# adapterplatine.net
KiCad netlist of a schematic drawn in EAGLE
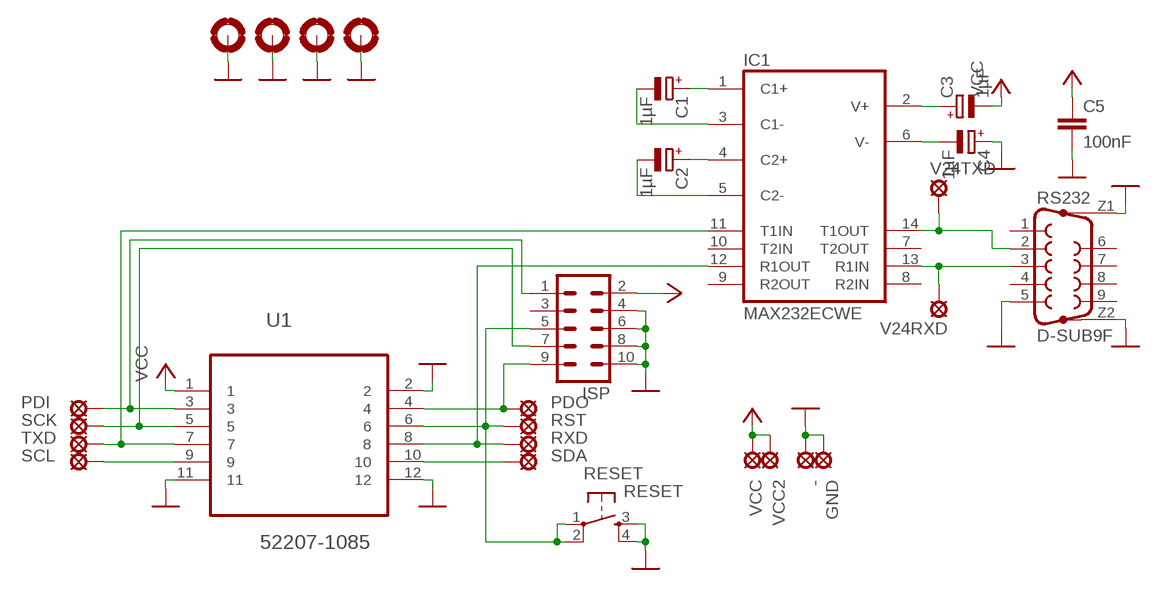
[diagram p0: schematic, sheet 1]

(export (version "E")
  (design (tool "Eeschema 10.0.6"))
  (components
    (comp (ref "-")
      (value "SE11")
      (footprint "eagle-import:SE11")
      (libsource (lib "eagle-import") (part "SE11"))
    )
    (comp (ref "C1")
      (value "1µF")
      (footprint "eagle-import:CT3216")
      (libsource (lib "eagle-import") (part "CPOL-EUCT3216"))
    )
    (comp (ref "C2")
      (value "1µF")
      (footprint "eagle-import:CT3216")
      (libsource (lib "eagle-import") (part "CPOL-EUCT3216"))
    )
    (comp (ref "C3")
      (value "1µF")
      (footprint "eagle-import:CT3216")
      (libsource (lib "eagle-import") (part "CPOL-EUCT3216"))
    )
    (comp (ref "C4")
      (value "1µF")
      (footprint "eagle-import:CT3216")
      (libsource (lib "eagle-import") (part "CPOL-EUCT3216"))
    )
    (comp (ref "C5")
      (value "100nF")
      (footprint "eagle-import:C1206")
      (libsource (lib "eagle-import") (part "C-EUC1206"))
    )
    (comp (ref "GND")
      (value "SE11")
      (footprint "eagle-import:SE11")
      (libsource (lib "eagle-import") (part "SE11"))
    )
    (comp (ref "IC1")
      (value "MAX232ECWE")
      (footprint "eagle-import:SO16L")
      (fields (field (name "MF") "MAXIM") (field (name "MPN") "MAX232ECWE+"))
      (libsource (lib "eagle-import") (part "MAX232ECWE"))
    )
    (comp (ref "ISP")
      (value "ML10")
      (footprint "eagle-import:ML10")
      (libsource (lib "eagle-import") (part "ML10"))
    )
    (comp (ref "PDI")
      (value "SE11")
      (footprint "eagle-import:SE11")
      (libsource (lib "eagle-import") (part "SE11"))
    )
    (comp (ref "PDO")
      (value "SE11")
      (footprint "eagle-import:SE11")
      (libsource (lib "eagle-import") (part "SE11"))
    )
    (comp (ref "RESET")
      (value "RESET")
      (footprint "eagle-import:TASTER")
      (libsource (lib "eagle-import") (part "TASTER"))
    )
    (comp (ref "RS232")
      (value "D-SUB9F")
      (footprint "eagle-import:D-SUB9F")
      (libsource (lib "eagle-import") (part "D-SUB9F"))
    )
    (comp (ref "RST")
      (value "SE11")
      (footprint "eagle-import:SE11")
      (libsource (lib "eagle-import") (part "SE11"))
    )
    (comp (ref "RXD")
      (value "SE11")
      (footprint "eagle-import:SE11")
      (libsource (lib "eagle-import") (part "SE11"))
    )
    (comp (ref "SCK")
      (value "SE11")
      (footprint "eagle-import:SE11")
      (libsource (lib "eagle-import") (part "SE11"))
    )
    (comp (ref "SCL")
      (value "SE11")
      (footprint "eagle-import:SE11")
      (libsource (lib "eagle-import") (part "SE11"))
    )
    (comp (ref "SDA")
      (value "SE11")
      (footprint "eagle-import:SE11")
      (libsource (lib "eagle-import") (part "SE11"))
    )
    (comp (ref "TXD")
      (value "SE11")
      (footprint "eagle-import:SE11")
      (libsource (lib "eagle-import") (part "SE11"))
    )
    (comp (ref "U$1")
      (value "LOCH")
      (footprint "eagle-import:LOCH")
      (libsource (lib "eagle-import") (part "LOCH"))
    )
    (comp (ref "U$2")
      (value "LOCH")
      (footprint "eagle-import:LOCH")
      (libsource (lib "eagle-import") (part "LOCH"))
    )
    (comp (ref "U$3")
      (value "LOCH")
      (footprint "eagle-import:LOCH")
      (libsource (lib "eagle-import") (part "LOCH"))
    )
    (comp (ref "U$4")
      (value "LOCH")
      (footprint "eagle-import:LOCH")
      (libsource (lib "eagle-import") (part "LOCH"))
    )
    (comp (ref "U1")
      (value "52207-1085")
      (footprint "eagle-import:MOLEX_52207-1085")
      (libsource (lib "eagle-import") (part "52207-1085"))
    )
    (comp (ref "V24RXD")
      (value "SE11")
      (footprint "eagle-import:SE11")
      (libsource (lib "eagle-import") (part "SE11"))
    )
    (comp (ref "V24TXD")
      (value "SE11")
      (footprint "eagle-import:SE11")
      (libsource (lib "eagle-import") (part "SE11"))
    )
    (comp (ref "VCC")
      (value "SE11")
      (footprint "eagle-import:SE11")
      (libsource (lib "eagle-import") (part "SE11"))
    )
    (comp (ref "VCC2")
      (value "SE11")
      (footprint "eagle-import:SE11")
      (libsource (lib "eagle-import") (part "SE11"))
    )
  )
  (nets
    (net (code "1") (name "GND") (class "Default")
      (node (ref "-") (pin "MP") (pinfunction "MP_MP") (pintype "passive"))
      (node (ref "C4") (pin "+") (pinfunction "+_+") (pintype "passive"))
      (node (ref "C5") (pin "2") (pinfunction "2_2") (pintype "passive"))
      (node (ref "GND") (pin "MP") (pinfunction "MP_MP") (pintype "passive"))
      (node (ref "ISP") (pin "10") (pinfunction "10_10") (pintype "passive"))
      (node (ref "ISP") (pin "4") (pinfunction "4_4") (pintype "passive"))
      (node (ref "ISP") (pin "6") (pinfunction "6_6") (pintype "passive"))
      (node (ref "ISP") (pin "8") (pinfunction "8_8") (pintype "passive"))
      (node (ref "RESET") (pin "3") (pinfunction "3_3") (pintype "passive"))
      (node (ref "RESET") (pin "4") (pinfunction "4_4") (pintype "passive"))
      (node (ref "RS232") (pin "5") (pinfunction "5_5") (pintype "passive"))
      (node (ref "RS232") (pin "Z1") (pinfunction "G1_Z1") (pintype "passive"))
      (node (ref "RS232") (pin "Z2") (pinfunction "G2_Z2") (pintype "passive"))
      (node (ref "U$1") (pin "B3,0") (pinfunction "MOUNT_B3,0") (pintype "passive"))
      (node (ref "U$2") (pin "B3,0") (pinfunction "MOUNT_B3,0") (pintype "passive"))
      (node (ref "U$3") (pin "B3,0") (pinfunction "MOUNT_B3,0") (pintype "passive"))
      (node (ref "U$4") (pin "B3,0") (pinfunction "MOUNT_B3,0") (pintype "passive"))
      (node (ref "U1") (pin "11") (pinfunction "11_11") (pintype "passive"))
      (node (ref "U1") (pin "12") (pinfunction "12_12") (pintype "passive"))
      (node (ref "U1") (pin "2") (pinfunction "2_2") (pintype "passive"))
    )
    (net (code "2") (name "Net-(IC1A-C1+)") (class "Default")
      (node (ref "C1") (pin "+") (pinfunction "+_+") (pintype "passive"))
      (node (ref "IC1") (pin "1") (pinfunction "C1+_1") (pintype "bidirectional"))
    )
    (net (code "3") (name "Net-(IC1A-C1-)") (class "Default")
      (node (ref "C1") (pin "-") (pinfunction "-_-") (pintype "passive"))
      (node (ref "IC1") (pin "3") (pinfunction "C1-_3") (pintype "bidirectional"))
    )
    (net (code "4") (name "Net-(IC1A-C2+)") (class "Default")
      (node (ref "C2") (pin "+") (pinfunction "+_+") (pintype "passive"))
      (node (ref "IC1") (pin "4") (pinfunction "C2+_4") (pintype "bidirectional"))
    )
    (net (code "5") (name "Net-(IC1A-C2-)") (class "Default")
      (node (ref "C2") (pin "-") (pinfunction "-_-") (pintype "passive"))
      (node (ref "IC1") (pin "5") (pinfunction "C2-_5") (pintype "bidirectional"))
    )
    (net (code "6") (name "Net-(IC1A-R1IN)") (class "Default")
      (node (ref "IC1") (pin "13") (pinfunction "R1IN_13") (pintype "input"))
      (node (ref "RS232") (pin "3") (pinfunction "3_3") (pintype "passive"))
      (node (ref "V24RXD") (pin "MP") (pinfunction "MP_MP") (pintype "passive"))
    )
    (net (code "7") (name "Net-(IC1A-R1OUT)") (class "Default")
      (node (ref "IC1") (pin "12") (pinfunction "R1OUT_12") (pintype "output"))
      (node (ref "RXD") (pin "MP") (pinfunction "MP_MP") (pintype "passive"))
      (node (ref "U1") (pin "8") (pinfunction "8_8") (pintype "passive"))
    )
    (net (code "8") (name "Net-(IC1A-T1IN)") (class "Default")
      (node (ref "IC1") (pin "11") (pinfunction "T1IN_11") (pintype "input"))
      (node (ref "TXD") (pin "MP") (pinfunction "MP_MP") (pintype "passive"))
      (node (ref "U1") (pin "7") (pinfunction "7_7") (pintype "passive"))
    )
    (net (code "9") (name "Net-(IC1A-T1OUT)") (class "Default")
      (node (ref "IC1") (pin "14") (pinfunction "T1OUT_14") (pintype "output"))
      (node (ref "RS232") (pin "2") (pinfunction "2_2") (pintype "passive"))
      (node (ref "V24TXD") (pin "MP") (pinfunction "MP_MP") (pintype "passive"))
    )
    (net (code "10") (name "Net-(IC1A-V+)") (class "Default")
      (node (ref "C3") (pin "+") (pinfunction "+_+") (pintype "passive"))
      (node (ref "IC1") (pin "2") (pinfunction "V+_2") (pintype "bidirectional"))
    )
    (net (code "11") (name "Net-(IC1A-V-)") (class "Default")
      (node (ref "C4") (pin "-") (pinfunction "-_-") (pintype "passive"))
      (node (ref "IC1") (pin "6") (pinfunction "V-_6") (pintype "bidirectional"))
    )
    (net (code "12") (name "Net-(ISP-Pad1)") (class "Default")
      (node (ref "ISP") (pin "1") (pinfunction "1_1") (pintype "passive"))
      (node (ref "PDI") (pin "MP") (pinfunction "MP_MP") (pintype "passive"))
      (node (ref "U1") (pin "3") (pinfunction "3_3") (pintype "passive"))
    )
    (net (code "13") (name "Net-(ISP-Pad5)") (class "Default")
      (node (ref "ISP") (pin "5") (pinfunction "5_5") (pintype "passive"))
      (node (ref "RESET") (pin "1") (pinfunction "1_1") (pintype "passive"))
      (node (ref "RESET") (pin "2") (pinfunction "2_2") (pintype "passive"))
      (node (ref "RST") (pin "MP") (pinfunction "MP_MP") (pintype "passive"))
      (node (ref "U1") (pin "6") (pinfunction "6_6") (pintype "passive"))
    )
    (net (code "14") (name "Net-(ISP-Pad7)") (class "Default")
      (node (ref "ISP") (pin "7") (pinfunction "7_7") (pintype "passive"))
      (node (ref "SCK") (pin "MP") (pinfunction "MP_MP") (pintype "passive"))
      (node (ref "U1") (pin "5") (pinfunction "5_5") (pintype "passive"))
    )
    (net (code "15") (name "Net-(ISP-Pad9)") (class "Default")
      (node (ref "ISP") (pin "9") (pinfunction "9_9") (pintype "passive"))
      (node (ref "PDO") (pin "MP") (pinfunction "MP_MP") (pintype "passive"))
      (node (ref "U1") (pin "4") (pinfunction "4_4") (pintype "passive"))
    )
    (net (code "16") (name "Net-(SCL-PadMP)") (class "Default")
      (node (ref "SCL") (pin "MP") (pinfunction "MP_MP") (pintype "passive"))
      (node (ref "U1") (pin "9") (pinfunction "9_9") (pintype "passive"))
    )
    (net (code "17") (name "Net-(SDA-PadMP)") (class "Default")
      (node (ref "SDA") (pin "MP") (pinfunction "MP_MP") (pintype "passive"))
      (node (ref "U1") (pin "10") (pinfunction "10_10") (pintype "passive"))
    )
    (net (code "18") (name "VCC") (class "Default")
      (node (ref "C3") (pin "-") (pinfunction "-_-") (pintype "passive"))
      (node (ref "C5") (pin "1") (pinfunction "1_1") (pintype "passive"))
      (node (ref "ISP") (pin "2") (pinfunction "2_2") (pintype "passive"))
      (node (ref "U1") (pin "1") (pinfunction "1_1") (pintype "passive"))
      (node (ref "VCC") (pin "MP") (pinfunction "MP_MP") (pintype "passive"))
      (node (ref "VCC2") (pin "MP") (pinfunction "MP_MP") (pintype "passive"))
    )
    (net (code "19") (name "unconnected-(IC1A-R2IN-Pad8)") (class "Default")
      (node (ref "IC1") (pin "8") (pinfunction "R2IN_8") (pintype "input"))
    )
    (net (code "20") (name "unconnected-(IC1A-R2OUT-Pad9)") (class "Default")
      (node (ref "IC1") (pin "9") (pinfunction "R2OUT_9") (pintype "output"))
    )
    (net (code "21") (name "unconnected-(IC1A-T2IN-Pad10)") (class "Default")
      (node (ref "IC1") (pin "10") (pinfunction "T2IN_10") (pintype "input"))
    )
    (net (code "22") (name "unconnected-(IC1A-T2OUT-Pad7)") (class "Default")
      (node (ref "IC1") (pin "7") (pinfunction "T2OUT_7") (pintype "output"))
    )
    (net (code "23") (name "unconnected-(ISP-Pad3)") (class "Default")
      (node (ref "ISP") (pin "3") (pinfunction "3_3") (pintype "passive"))
    )
    (net (code "24") (name "unconnected-(RS232-Pad1)") (class "Default")
      (node (ref "RS232") (pin "1") (pinfunction "1_1") (pintype "passive"))
    )
    (net (code "25") (name "unconnected-(RS232-Pad4)") (class "Default")
      (node (ref "RS232") (pin "4") (pinfunction "4_4") (pintype "passive"))
    )
    (net (code "26") (name "unconnected-(RS232-Pad6)") (class "Default")
      (node (ref "RS232") (pin "6") (pinfunction "6_6") (pintype "passive"))
    )
    (net (code "27") (name "unconnected-(RS232-Pad7)") (class "Default")
      (node (ref "RS232") (pin "7") (pinfunction "7_7") (pintype "passive"))
    )
    (net (code "28") (name "unconnected-(RS232-Pad8)") (class "Default")
      (node (ref "RS232") (pin "8") (pinfunction "8_8") (pintype "passive"))
    )
    (net (code "29") (name "unconnected-(RS232-Pad9)") (class "Default")
      (node (ref "RS232") (pin "9") (pinfunction "9_9") (pintype "passive"))
    )
  )
)
